# Battery_MGMT.net
KiCad netlist of a schematic drawn in Altium Designer
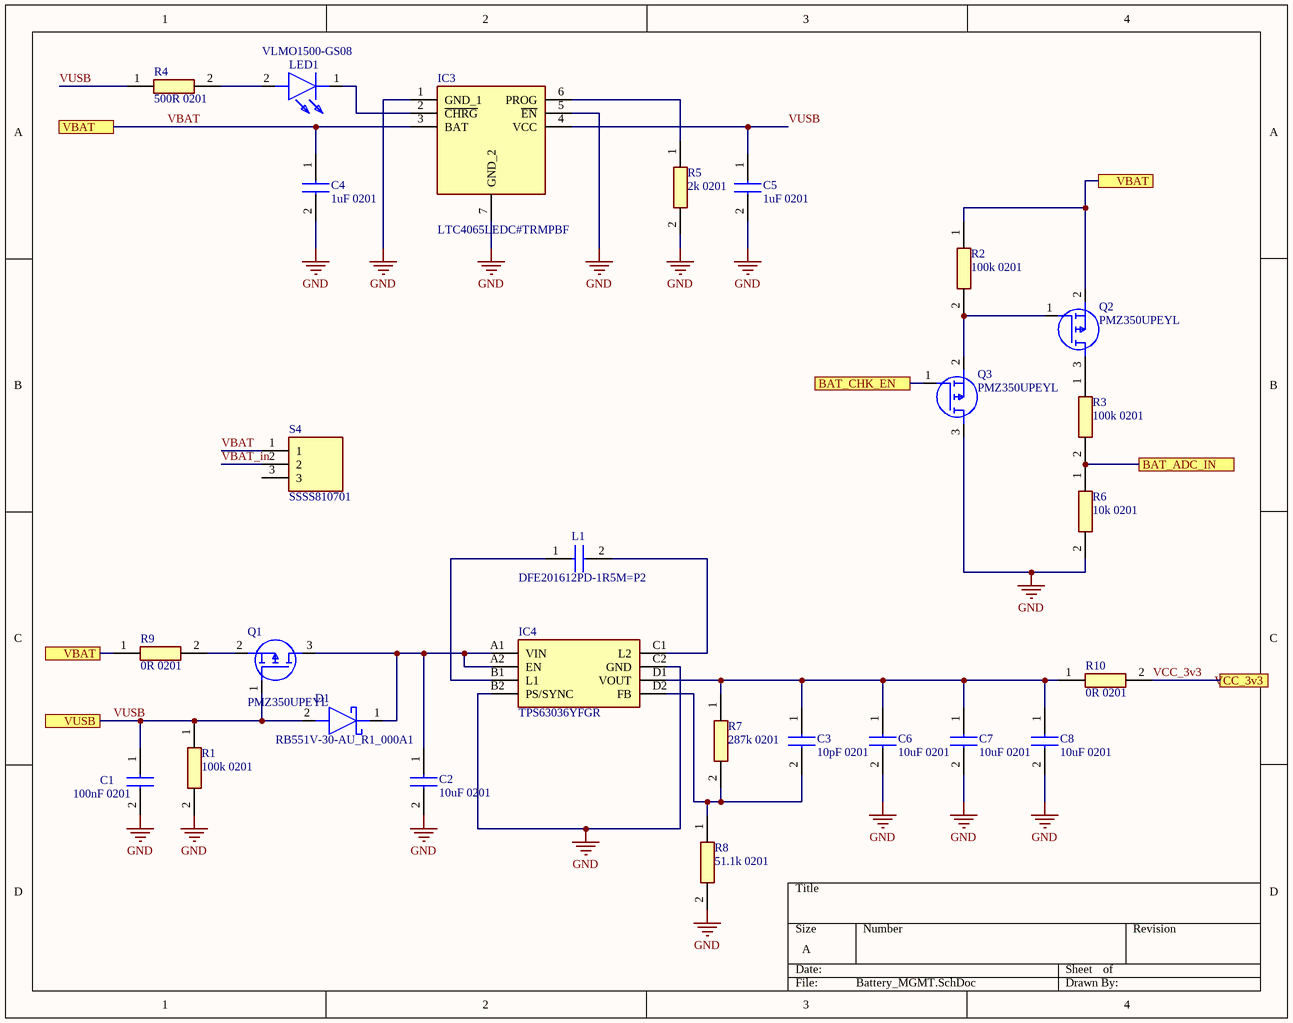
[diagram p0: Battery_MGMT.SchDoc]

(export (version "E")
  (design (tool "Eeschema 10.0.6"))
  (components
    (comp (ref "C1")
      (value "100nF 0201")
      (footprint "SamacSys:CAPC0603X33N")
      (description "Capacitor")
      (fields
        (field (name "MANUFACTURER_PART_NUMBER") "02013A0R5BAT2A")
        (field (name "MOUSER PART NUMBER") "581-02013A0R5BAT2A")
      )
      (libsource (lib "*") (part "02013A0R5BAT2A"))
    )
    (comp (ref "C2")
      (value "10uF 0201")
      (footprint "SamacSys:CAPC0603X33N")
      (description "Capacitor")
      (fields
        (field (name "MANUFACTURER_PART_NUMBER") "02013A0R5BAT2A")
        (field (name "MOUSER PART NUMBER") "581-02013A0R5BAT2A")
      )
      (libsource (lib "*") (part "02013A0R5BAT2A"))
    )
    (comp (ref "C3")
      (value "10pF 0201")
      (footprint "SamacSys:CAPC0603X33N")
      (description "Capacitor")
      (fields
        (field (name "MANUFACTURER_PART_NUMBER") "02013A0R5BAT2A")
        (field (name "MOUSER PART NUMBER") "581-02013A0R5BAT2A")
      )
      (libsource (lib "*") (part "02013A0R5BAT2A"))
    )
    (comp (ref "C4")
      (value "1uF 0201")
      (footprint "SamacSys:CAPC0603X33N")
      (description "Capacitor")
      (fields
        (field (name "MANUFACTURER_PART_NUMBER") "02013A0R5BAT2A")
        (field (name "MOUSER PART NUMBER") "581-02013A0R5BAT2A")
      )
      (libsource (lib "*") (part "02013A0R5BAT2A"))
    )
    (comp (ref "C5")
      (value "1uF 0201")
      (footprint "SamacSys:CAPC0603X33N")
      (description "Capacitor")
      (fields
        (field (name "MANUFACTURER_PART_NUMBER") "02013A0R5BAT2A")
        (field (name "MOUSER PART NUMBER") "581-02013A0R5BAT2A")
      )
      (libsource (lib "*") (part "02013A0R5BAT2A"))
    )
    (comp (ref "C6")
      (value "10uF 0201")
      (footprint "SamacSys:CAPC0603X33N")
      (description "Capacitor")
      (fields
        (field (name "MANUFACTURER_PART_NUMBER") "02013A0R5BAT2A")
        (field (name "MOUSER PART NUMBER") "581-02013A0R5BAT2A")
      )
      (libsource (lib "*") (part "02013A0R5BAT2A"))
    )
    (comp (ref "C7")
      (value "10uF 0201")
      (footprint "SamacSys:CAPC0603X33N")
      (description "Capacitor")
      (fields
        (field (name "MANUFACTURER_PART_NUMBER") "02013A0R5BAT2A")
        (field (name "MOUSER PART NUMBER") "581-02013A0R5BAT2A")
      )
      (libsource (lib "*") (part "02013A0R5BAT2A"))
    )
    (comp (ref "C8")
      (value "10uF 0201")
      (footprint "SamacSys:CAPC0603X33N")
      (description "Capacitor")
      (fields
        (field (name "MANUFACTURER_PART_NUMBER") "02013A0R5BAT2A")
        (field (name "MOUSER PART NUMBER") "581-02013A0R5BAT2A")
      )
      (libsource (lib "*") (part "02013A0R5BAT2A"))
    )
    (comp (ref "D1")
      (value "RB551V-30-AU_R1_000A1")
      (footprint "SamacSys:SODFL2512X90N")
      (description "Schottky Diode")
      (fields (field (name "MOUSER PART NUMBER") "241-RB551V30AUR1000A"))
      (libsource (lib "*") (part "RB551V-30-AU_R1_000A1"))
    )
    (comp (ref "IC3")
      (value "LTC4065LEDC#TRMPBF")
      (footprint "SamacSys:SON50P200X200X80-7N-D")
      (description "Integrated Circuit")
      (fields (field (name "MOUSER PART NUMBER") "584-C4065LEDCTRMPBF"))
      (libsource (lib "*") (part "LTC4065LEDC#TRMPBF"))
    )
    (comp (ref "IC4")
      (value "TPS63036YFGR")
      (footprint "SamacSys:BGA8C40P2X4_108X181X62")
      (description "Integrated Circuit")
      (fields (field (name "MOUSER PART NUMBER") "595-TPS63036YFGR"))
      (libsource (lib "*") (part "TPS63036YFGR"))
    )
    (comp (ref "L1")
      (value "DFE201612PD-1R5M=P2")
      (footprint "SamacSys:1286ASH1R0MP2")
      (description "Capacitor")
      (fields (field (name "MOUSER PART NUMBER") "81-DFE201612PD1R5P2"))
      (libsource (lib "*") (part "DFE201612PD-1R5M=P2"))
    )
    (comp (ref "LED1")
      (value "VLMO1500-GS08")
      (footprint "SamacSys:VLMO1500GS08")
      (description "LED")
      (fields (field (name "MOUSER PART NUMBER") "78-VLMO1500-GS08"))
      (libsource (lib "*") (part "VLMO1500-GS08"))
    )
    (comp (ref "Q1")
      (value "PMZ350UPEYL")
      (footprint "SamacSys:PMZ350UPEYL")
      (description "MOSFET (P-Channel)")
      (fields (field (name "MOUSER PART NUMBER") "771-PMZ350UPEYL"))
      (libsource (lib "*") (part "PMZ350UPEYL"))
    )
    (comp (ref "Q2")
      (value "PMZ350UPEYL")
      (footprint "SamacSys:PMZ350UPEYL")
      (description "MOSFET (P-Channel)")
      (fields (field (name "MOUSER PART NUMBER") "771-PMZ350UPEYL"))
      (libsource (lib "*") (part "PMZ350UPEYL"))
    )
    (comp (ref "Q3")
      (value "PMZ350UPEYL")
      (footprint "SamacSys:PMZ350UPEYL")
      (description "MOSFET (P-Channel)")
      (fields (field (name "MOUSER PART NUMBER") "771-PMZ350UPEYL"))
      (libsource (lib "*") (part "PMZ350UPEYL"))
    )
    (comp (ref "R1")
      (value "100k 0201")
      (footprint "SamacSys:RESC0603X28N")
      (description "Resistor")
      (fields (field (name "MANUFACTURER_PART_NUMBER") "CPF0201D422RE1"))
      (libsource (lib "*") (part "CPF0201D422RE1"))
    )
    (comp (ref "R2")
      (value "100k 0201")
      (footprint "SamacSys:RESC0603X28N")
      (description "Resistor")
      (fields (field (name "MANUFACTURER_PART_NUMBER") "CPF0201D422RE1"))
      (libsource (lib "*") (part "CPF0201D422RE1"))
    )
    (comp (ref "R3")
      (value "100k 0201")
      (footprint "SamacSys:RESC0603X28N")
      (description "Resistor")
      (fields (field (name "MANUFACTURER_PART_NUMBER") "CPF0201D422RE1"))
      (libsource (lib "*") (part "CPF0201D422RE1"))
    )
    (comp (ref "R4")
      (value "500R 0201")
      (footprint "SamacSys:RESC0603X28N")
      (description "Resistor")
      (fields (field (name "MANUFACTURER_PART_NUMBER") "CPF0201D422RE1"))
      (libsource (lib "") (part "CPF0201D422RE1_1"))
    )
    (comp (ref "R5")
      (value "2k 0201")
      (footprint "SamacSys:RESC0603X28N")
      (description "Resistor")
      (fields (field (name "MANUFACTURER_PART_NUMBER") "CPF0201D422RE1"))
      (libsource (lib "*") (part "CPF0201D422RE1"))
    )
    (comp (ref "R6")
      (value "10k 0201")
      (footprint "SamacSys:RESC0603X28N")
      (description "Resistor")
      (fields (field (name "MANUFACTURER_PART_NUMBER") "CPF0201D422RE1"))
      (libsource (lib "*") (part "CPF0201D422RE1"))
    )
    (comp (ref "R7")
      (value "287k 0201")
      (footprint "SamacSys:RESC0603X28N")
      (description "Resistor")
      (fields (field (name "MANUFACTURER_PART_NUMBER") "CPF0201D422RE1"))
      (libsource (lib "*") (part "CPF0201D422RE1"))
    )
    (comp (ref "R8")
      (value "51.1k 0201")
      (footprint "SamacSys:RESC0603X28N")
      (description "Resistor")
      (fields (field (name "MANUFACTURER_PART_NUMBER") "CPF0201D422RE1"))
      (libsource (lib "*") (part "CPF0201D422RE1"))
    )
    (comp (ref "R9")
      (value "0R 0201")
      (footprint "SamacSys:RESC0603X28N")
      (description "Resistor")
      (fields (field (name "MANUFACTURER_PART_NUMBER") "CPF0201D422RE1"))
      (libsource (lib "") (part "CPF0201D422RE1_1"))
    )
    (comp (ref "R10")
      (value "0R 0201")
      (footprint "SamacSys:RESC0603X28N")
      (description "Resistor")
      (fields (field (name "MANUFACTURER_PART_NUMBER") "CPF0201D422RE1"))
      (libsource (lib "") (part "CPF0201D422RE1_1"))
    )
    (comp (ref "S4")
      (value "SSSS810701")
      (footprint "SamacSys:SSSS810701")
      (description "Switch")
      (fields (field (name "MOUSER PART NUMBER") "688-SSSS810701"))
      (libsource (lib "*") (part "SSSS810701"))
    )
  )
  (nets
    (net (code "1") (name "/BAT_ADC_IN") (class "Default")
      (node (ref "R3") (pin "2") (pinfunction "2_2") (pintype "passive"))
      (node (ref "R6") (pin "1") (pinfunction "1_1") (pintype "passive"))
    )
    (net (code "2") (name "/BAT_CHK_EN") (class "Default")
      (node (ref "Q3") (pin "1") (pinfunction "G_1") (pintype "passive"))
    )
    (net (code "3") (name "/VBAT") (class "Default")
      (node (ref "C4") (pin "1") (pinfunction "1_1") (pintype "passive"))
      (node (ref "IC3") (pin "3") (pinfunction "BAT_3") (pintype "passive"))
      (node (ref "Q2") (pin "2") (pinfunction "S_2") (pintype "passive"))
      (node (ref "R2") (pin "1") (pinfunction "1_1") (pintype "passive"))
      (node (ref "R9") (pin "1") (pinfunction "1_1") (pintype "passive"))
      (node (ref "S4") (pin "1") (pinfunction "1_1") (pintype "passive"))
    )
    (net (code "4") (name "/VBAT_in") (class "Default")
      (node (ref "S4") (pin "2") (pinfunction "2_2") (pintype "passive"))
    )
    (net (code "5") (name "/VCC_3v3") (class "Default")
      (node (ref "R10") (pin "2") (pinfunction "2_2") (pintype "passive"))
    )
    (net (code "6") (name "/VUSB") (class "Default")
      (node (ref "C1") (pin "1") (pinfunction "1_1") (pintype "passive"))
      (node (ref "C5") (pin "1") (pinfunction "1_1") (pintype "passive"))
      (node (ref "D1") (pin "2") (pinfunction "A_2") (pintype "passive"))
      (node (ref "IC3") (pin "4") (pinfunction "VCC_4") (pintype "passive"))
      (node (ref "Q1") (pin "1") (pinfunction "G_1") (pintype "passive"))
      (node (ref "R1") (pin "1") (pinfunction "1_1") (pintype "passive"))
      (node (ref "R4") (pin "1") (pinfunction "1_1") (pintype "passive"))
    )
    (net (code "7") (name "GND") (class "Default")
      (node (ref "C1") (pin "2") (pinfunction "2_2") (pintype "passive"))
      (node (ref "C2") (pin "2") (pinfunction "2_2") (pintype "passive"))
      (node (ref "C4") (pin "2") (pinfunction "2_2") (pintype "passive"))
      (node (ref "C5") (pin "2") (pinfunction "2_2") (pintype "passive"))
      (node (ref "C6") (pin "2") (pinfunction "2_2") (pintype "passive"))
      (node (ref "C7") (pin "2") (pinfunction "2_2") (pintype "passive"))
      (node (ref "C8") (pin "2") (pinfunction "2_2") (pintype "passive"))
      (node (ref "IC3") (pin "1") (pinfunction "GND_1_1") (pintype "passive"))
      (node (ref "IC3") (pin "5") (pinfunction "~{EN}_5") (pintype "passive"))
      (node (ref "IC3") (pin "7") (pinfunction "GND_2_7") (pintype "passive"))
      (node (ref "IC4") (pin "B2") (pinfunction "PS/SYNC_B2") (pintype "passive"))
      (node (ref "IC4") (pin "C2") (pinfunction "GND_C2") (pintype "passive"))
      (node (ref "Q3") (pin "3") (pinfunction "D_3") (pintype "passive"))
      (node (ref "R1") (pin "2") (pinfunction "2_2") (pintype "passive"))
      (node (ref "R5") (pin "2") (pinfunction "2_2") (pintype "passive"))
      (node (ref "R6") (pin "2") (pinfunction "2_2") (pintype "passive"))
      (node (ref "R8") (pin "2") (pinfunction "2_2") (pintype "passive"))
    )
    (net (code "8") (name "Net-(D1-K)") (class "Default")
      (node (ref "C2") (pin "1") (pinfunction "1_1") (pintype "passive"))
      (node (ref "D1") (pin "1") (pinfunction "K_1") (pintype "passive"))
      (node (ref "IC4") (pin "A1") (pinfunction "VIN_A1") (pintype "passive"))
      (node (ref "IC4") (pin "A2") (pinfunction "EN_A2") (pintype "passive"))
      (node (ref "Q1") (pin "3") (pinfunction "D_3") (pintype "passive"))
    )
    (net (code "9") (name "Net-(IC3-PROG)") (class "Default")
      (node (ref "IC3") (pin "6") (pinfunction "PROG_6") (pintype "passive"))
      (node (ref "R5") (pin "1") (pinfunction "1_1") (pintype "passive"))
    )
    (net (code "10") (name "Net-(IC3-~{CHRG})") (class "Default")
      (node (ref "IC3") (pin "2") (pinfunction "~{CHRG}_2") (pintype "passive"))
      (node (ref "LED1") (pin "1") (pinfunction "K_1") (pintype "passive"))
    )
    (net (code "11") (name "Net-(IC4-FB)") (class "Default")
      (node (ref "C3") (pin "2") (pinfunction "2_2") (pintype "passive"))
      (node (ref "IC4") (pin "D2") (pinfunction "FB_D2") (pintype "passive"))
      (node (ref "R7") (pin "2") (pinfunction "2_2") (pintype "passive"))
      (node (ref "R8") (pin "1") (pinfunction "1_1") (pintype "passive"))
    )
    (net (code "12") (name "Net-(IC4-L1)") (class "Default")
      (node (ref "IC4") (pin "B1") (pinfunction "L1_B1") (pintype "passive"))
      (node (ref "L1") (pin "1") (pinfunction "1_1") (pintype "passive"))
    )
    (net (code "13") (name "Net-(IC4-L2)") (class "Default")
      (node (ref "IC4") (pin "C1") (pinfunction "L2_C1") (pintype "passive"))
      (node (ref "L1") (pin "2") (pinfunction "2_2") (pintype "passive"))
    )
    (net (code "14") (name "Net-(IC4-VOUT)") (class "Default")
      (node (ref "C3") (pin "1") (pinfunction "1_1") (pintype "passive"))
      (node (ref "C6") (pin "1") (pinfunction "1_1") (pintype "passive"))
      (node (ref "C7") (pin "1") (pinfunction "1_1") (pintype "passive"))
      (node (ref "C8") (pin "1") (pinfunction "1_1") (pintype "passive"))
      (node (ref "IC4") (pin "D1") (pinfunction "VOUT_D1") (pintype "passive"))
      (node (ref "R10") (pin "1") (pinfunction "1_1") (pintype "passive"))
      (node (ref "R7") (pin "1") (pinfunction "1_1") (pintype "passive"))
    )
    (net (code "15") (name "Net-(LED1-A)") (class "Default")
      (node (ref "LED1") (pin "2") (pinfunction "A_2") (pintype "passive"))
      (node (ref "R4") (pin "2") (pinfunction "2_2") (pintype "passive"))
    )
    (net (code "16") (name "Net-(Q1-S)") (class "Default")
      (node (ref "Q1") (pin "2") (pinfunction "S_2") (pintype "passive"))
      (node (ref "R9") (pin "2") (pinfunction "2_2") (pintype "passive"))
    )
    (net (code "17") (name "Net-(Q2-D)") (class "Default")
      (node (ref "Q2") (pin "3") (pinfunction "D_3") (pintype "passive"))
      (node (ref "R3") (pin "1") (pinfunction "1_1") (pintype "passive"))
    )
    (net (code "18") (name "Net-(Q2-G)") (class "Default")
      (node (ref "Q2") (pin "1") (pinfunction "G_1") (pintype "passive"))
      (node (ref "Q3") (pin "2") (pinfunction "S_2") (pintype "passive"))
      (node (ref "R2") (pin "2") (pinfunction "2_2") (pintype "passive"))
    )
    (net (code "19") (name "unconnected-(S4-Pad3)") (class "Default")
      (node (ref "S4") (pin "3") (pinfunction "3_3") (pintype "passive"))
    )
  )
)
